# Adafruit_NeoPXL8_Wing.net
KiCad netlist of a schematic drawn in EAGLE
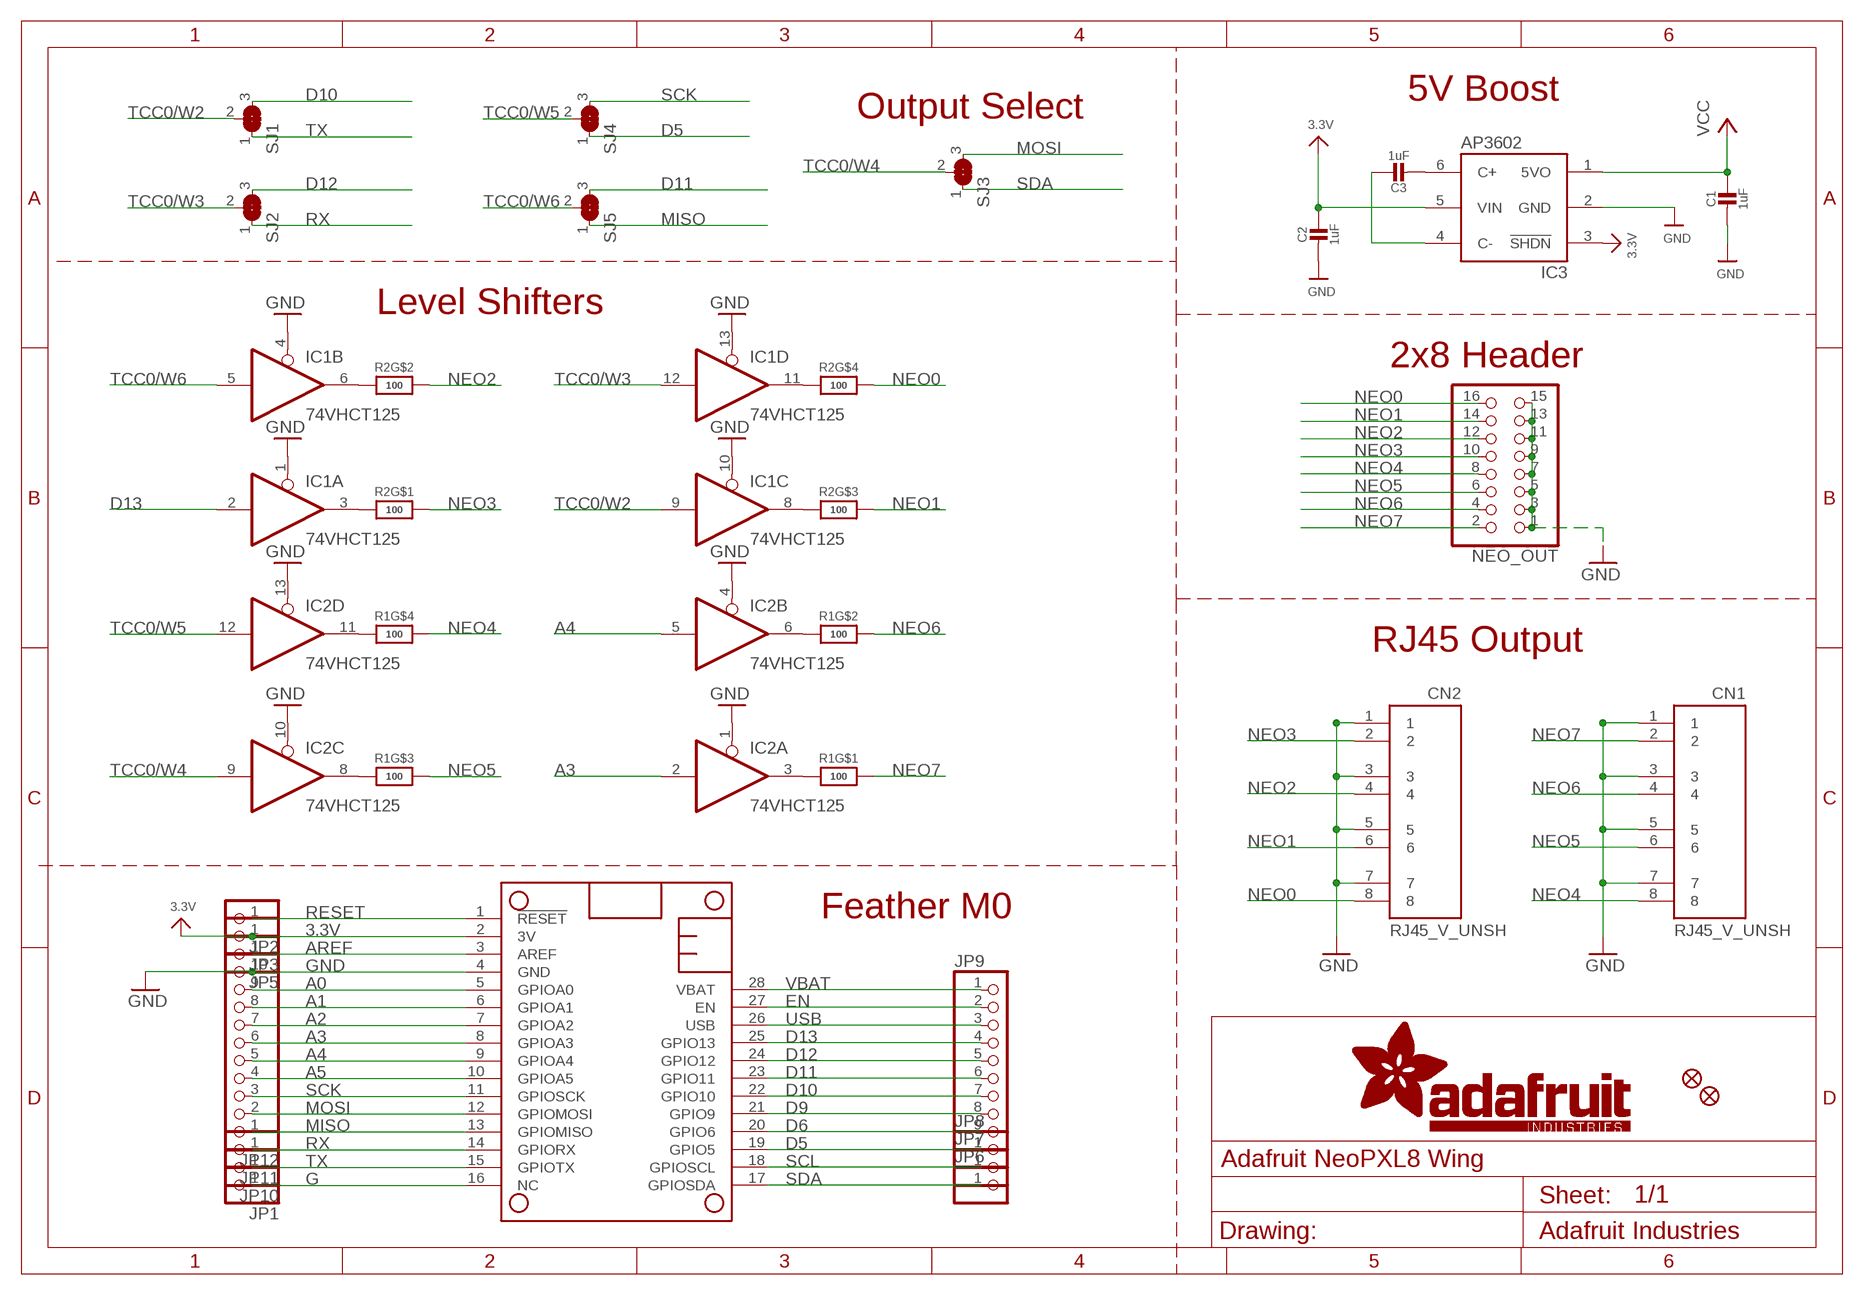
[diagram p0: schematic, sheet 1]

(export (version "E")
  (design (tool "Eeschema 10.0.6"))
  (components
    (comp (ref "C1")
      (value "1uF")
      (footprint "eagle-import:0603-NO")
      (libsource (lib "eagle-import") (part "CAP_CERAMIC0603_NO"))
    )
    (comp (ref "C2")
      (value "1uF")
      (footprint "eagle-import:0603-NO")
      (libsource (lib "eagle-import") (part "CAP_CERAMIC0603_NO"))
    )
    (comp (ref "C3")
      (value "1uF")
      (footprint "eagle-import:0603-NO")
      (libsource (lib "eagle-import") (part "CAP_CERAMIC0603_NO"))
    )
    (comp (ref "CN1")
      (value "RJ45_V_UNSH")
      (footprint "eagle-import:RJ45_VERTICAL_UNSHIELDED")
      (libsource (lib "eagle-import") (part "RJ45_V_UNSH"))
    )
    (comp (ref "CN2")
      (value "RJ45_V_UNSH")
      (footprint "eagle-import:RJ45_VERTICAL_UNSHIELDED")
      (libsource (lib "eagle-import") (part "RJ45_V_UNSH"))
    )
    (comp (ref "FID1")
      (value "FIDUCIAL_1MM")
      (footprint "eagle-import:FIDUCIAL_1MM")
      (libsource (lib "eagle-import") (part "FIDUCIAL_1MM"))
    )
    (comp (ref "FID2")
      (value "FIDUCIAL_1MM")
      (footprint "eagle-import:FIDUCIAL_1MM")
      (libsource (lib "eagle-import") (part "FIDUCIAL_1MM"))
    )
    (comp (ref "IC1")
      (value "74VHCT125")
      (footprint "eagle-import:TSSOP14")
      (libsource (lib "eagle-import") (part "74125PWABT"))
    )
    (comp (ref "IC2")
      (value "74VHCT125")
      (footprint "eagle-import:TSSOP14")
      (libsource (lib "eagle-import") (part "74125PWABT"))
    )
    (comp (ref "IC3")
      (value "AP3602")
      (footprint "eagle-import:SOT23-6")
      (libsource (lib "eagle-import") (part "AP3602"))
    )
    (comp (ref "JP1")
      (value "HEADER-1X1ROUND")
      (footprint "eagle-import:1X01_ROUND")
      (libsource (lib "eagle-import") (part "HEADER-1X1ROUND"))
    )
    (comp (ref "JP2")
      (value "HEADER-1X1ROUND")
      (footprint "eagle-import:1X01_ROUND")
      (libsource (lib "eagle-import") (part "HEADER-1X1ROUND"))
    )
    (comp (ref "JP3")
      (value "HEADER-1X1ROUND")
      (footprint "eagle-import:1X01_ROUND")
      (libsource (lib "eagle-import") (part "HEADER-1X1ROUND"))
    )
    (comp (ref "JP5")
      (value "HEADER-1X1ROUND")
      (footprint "eagle-import:1X01_ROUND")
      (libsource (lib "eagle-import") (part "HEADER-1X1ROUND"))
    )
    (comp (ref "JP6")
      (value "HEADER-1X1ROUND")
      (footprint "eagle-import:1X01_ROUND")
      (libsource (lib "eagle-import") (part "HEADER-1X1ROUND"))
    )
    (comp (ref "JP7")
      (value "HEADER-1X1ROUND")
      (footprint "eagle-import:1X01_ROUND")
      (libsource (lib "eagle-import") (part "HEADER-1X1ROUND"))
    )
    (comp (ref "JP8")
      (value "HEADER-1X1ROUND")
      (footprint "eagle-import:1X01_ROUND")
      (libsource (lib "eagle-import") (part "HEADER-1X1ROUND"))
    )
    (comp (ref "JP9")
      (value "HEADER-1X970MIL")
      (footprint "eagle-import:1X09_ROUND_70")
      (libsource (lib "eagle-import") (part "HEADER-1X970MIL"))
    )
    (comp (ref "JP10")
      (value "HEADER-1X1ROUND")
      (footprint "eagle-import:1X01_ROUND")
      (libsource (lib "eagle-import") (part "HEADER-1X1ROUND"))
    )
    (comp (ref "JP11")
      (value "HEADER-1X1ROUND")
      (footprint "eagle-import:1X01_ROUND")
      (libsource (lib "eagle-import") (part "HEADER-1X1ROUND"))
    )
    (comp (ref "JP12")
      (value "HEADER-1X10ROUND")
      (footprint "eagle-import:1X10_ROUND")
      (libsource (lib "eagle-import") (part "HEADER-1X10ROUND"))
    )
    (comp (ref "MS1")
      (value "FEATHERWING")
      (footprint "eagle-import:FEATHERWING")
      (libsource (lib "eagle-import") (part "FEATHERWING"))
    )
    (comp (ref "NEO_OUT")
      (value "HEADER-2X8")
      (footprint "eagle-import:2X08")
      (libsource (lib "eagle-import") (part "HEADER-2X8"))
    )
    (comp (ref "R1")
      (value "100")
      (footprint "eagle-import:RESPACK_4X0603")
      (libsource (lib "eagle-import") (part "RESISTOR_4PACK"))
    )
    (comp (ref "R2")
      (value "100")
      (footprint "eagle-import:RESPACK_4X0603")
      (libsource (lib "eagle-import") (part "RESISTOR_4PACK"))
    )
    (comp (ref "SJ1")
      (value "SOLDERJUMPER_2WAY")
      (footprint "eagle-import:SOLDERJUMPER_2WAY_OPEN_NOPASTE")
      (libsource (lib "eagle-import") (part "SOLDERJUMPER_2WAY"))
    )
    (comp (ref "SJ2")
      (value "SOLDERJUMPER_2WAY")
      (footprint "eagle-import:SOLDERJUMPER_2WAY_OPEN_NOPASTE")
      (libsource (lib "eagle-import") (part "SOLDERJUMPER_2WAY"))
    )
    (comp (ref "SJ3")
      (value "SOLDERJUMPER_2WAY")
      (footprint "eagle-import:SOLDERJUMPER_2WAY_OPEN_NOPASTE")
      (libsource (lib "eagle-import") (part "SOLDERJUMPER_2WAY"))
    )
    (comp (ref "SJ4")
      (value "SOLDERJUMPER_2WAY")
      (footprint "eagle-import:SOLDERJUMPER_2WAY_OPEN_NOPASTE")
      (libsource (lib "eagle-import") (part "SOLDERJUMPER_2WAY"))
    )
    (comp (ref "SJ5")
      (value "SOLDERJUMPER_2WAY")
      (footprint "eagle-import:SOLDERJUMPER_2WAY_OPEN_NOPASTE")
      (libsource (lib "eagle-import") (part "SOLDERJUMPER_2WAY"))
    )
  )
  (nets
    (net (code "1") (name "/A0") (class "Default")
      (node (ref "JP12") (pin "9") (pinfunction "9_9") (pintype "passive"))
      (node (ref "MS1") (pin "5") (pinfunction "GPIOA0_5") (pintype "bidirectional"))
    )
    (net (code "2") (name "/A1") (class "Default")
      (node (ref "JP12") (pin "8") (pinfunction "8_8") (pintype "passive"))
      (node (ref "MS1") (pin "6") (pinfunction "GPIOA1_6") (pintype "bidirectional"))
    )
    (net (code "3") (name "/A2") (class "Default")
      (node (ref "JP12") (pin "7") (pinfunction "7_7") (pintype "passive"))
      (node (ref "MS1") (pin "7") (pinfunction "GPIOA2_7") (pintype "bidirectional"))
    )
    (net (code "4") (name "/A3") (class "Default")
      (node (ref "IC2") (pin "2") (pinfunction "I_2") (pintype "input"))
      (node (ref "JP12") (pin "6") (pinfunction "6_6") (pintype "passive"))
      (node (ref "MS1") (pin "8") (pinfunction "GPIOA3_8") (pintype "bidirectional"))
    )
    (net (code "5") (name "/A4") (class "Default")
      (node (ref "IC2") (pin "5") (pinfunction "I_5") (pintype "input"))
      (node (ref "JP12") (pin "5") (pinfunction "5_5") (pintype "passive"))
      (node (ref "MS1") (pin "9") (pinfunction "GPIOA4_9") (pintype "bidirectional"))
    )
    (net (code "6") (name "/A5") (class "Default")
      (node (ref "JP12") (pin "4") (pinfunction "4_4") (pintype "passive"))
      (node (ref "MS1") (pin "10") (pinfunction "GPIOA5_10") (pintype "bidirectional"))
    )
    (net (code "7") (name "/AREF") (class "Default")
      (node (ref "JP5") (pin "1") (pinfunction "1_1") (pintype "passive"))
      (node (ref "MS1") (pin "3") (pinfunction "AREF_3") (pintype "passive"))
    )
    (net (code "8") (name "/D5") (class "Default")
      (node (ref "JP8") (pin "1") (pinfunction "1_1") (pintype "passive"))
      (node (ref "MS1") (pin "19") (pinfunction "GPIO5_19") (pintype "bidirectional"))
      (node (ref "SJ4") (pin "1") (pinfunction "1_1") (pintype "passive"))
    )
    (net (code "9") (name "/D6") (class "Default")
      (node (ref "JP9") (pin "9") (pinfunction "9_9") (pintype "passive"))
      (node (ref "MS1") (pin "20") (pinfunction "GPIO6_20") (pintype "bidirectional"))
    )
    (net (code "10") (name "/D9") (class "Default")
      (node (ref "JP9") (pin "8") (pinfunction "8_8") (pintype "passive"))
      (node (ref "MS1") (pin "21") (pinfunction "GPIO9_21") (pintype "bidirectional"))
    )
    (net (code "11") (name "/D10") (class "Default")
      (node (ref "JP9") (pin "7") (pinfunction "7_7") (pintype "passive"))
      (node (ref "MS1") (pin "22") (pinfunction "GPIO10_22") (pintype "bidirectional"))
      (node (ref "SJ1") (pin "3") (pinfunction "3_3") (pintype "passive"))
    )
    (net (code "12") (name "/D11") (class "Default")
      (node (ref "JP9") (pin "6") (pinfunction "6_6") (pintype "passive"))
      (node (ref "MS1") (pin "23") (pinfunction "GPIO11_23") (pintype "bidirectional"))
      (node (ref "SJ5") (pin "3") (pinfunction "3_3") (pintype "passive"))
    )
    (net (code "13") (name "/D12") (class "Default")
      (node (ref "JP9") (pin "5") (pinfunction "5_5") (pintype "passive"))
      (node (ref "MS1") (pin "24") (pinfunction "GPIO12_24") (pintype "bidirectional"))
      (node (ref "SJ2") (pin "3") (pinfunction "3_3") (pintype "passive"))
    )
    (net (code "14") (name "/D13") (class "Default")
      (node (ref "IC1") (pin "2") (pinfunction "I_2") (pintype "input"))
      (node (ref "JP9") (pin "4") (pinfunction "4_4") (pintype "passive"))
      (node (ref "MS1") (pin "25") (pinfunction "GPIO13_25") (pintype "bidirectional"))
    )
    (net (code "15") (name "/EN") (class "Default")
      (node (ref "JP9") (pin "2") (pinfunction "2_2") (pintype "passive"))
      (node (ref "MS1") (pin "27") (pinfunction "EN_27") (pintype "passive"))
    )
    (net (code "16") (name "/G") (class "Default")
      (node (ref "JP1") (pin "1") (pinfunction "1_1") (pintype "passive"))
      (node (ref "MS1") (pin "16") (pinfunction "NC_16") (pintype "passive"))
    )
    (net (code "17") (name "/MISO") (class "Default")
      (node (ref "JP12") (pin "1") (pinfunction "1_1") (pintype "passive"))
      (node (ref "MS1") (pin "13") (pinfunction "GPIOMISO_13") (pintype "bidirectional"))
      (node (ref "SJ5") (pin "1") (pinfunction "1_1") (pintype "passive"))
    )
    (net (code "18") (name "/MOSI") (class "Default")
      (node (ref "JP12") (pin "2") (pinfunction "2_2") (pintype "passive"))
      (node (ref "MS1") (pin "12") (pinfunction "GPIOMOSI_12") (pintype "bidirectional"))
      (node (ref "SJ3") (pin "3") (pinfunction "3_3") (pintype "passive"))
    )
    (net (code "19") (name "/NEO0") (class "Default")
      (node (ref "CN2") (pin "8") (pinfunction "8_8") (pintype "bidirectional"))
      (node (ref "NEO_OUT") (pin "16") (pinfunction "16_16") (pintype "passive"))
      (node (ref "R2") (pin "5") (pinfunction "2_5") (pintype "passive"))
    )
    (net (code "20") (name "/NEO1") (class "Default")
      (node (ref "CN2") (pin "6") (pinfunction "6_6") (pintype "bidirectional"))
      (node (ref "NEO_OUT") (pin "14") (pinfunction "14_14") (pintype "passive"))
      (node (ref "R2") (pin "6") (pinfunction "2_6") (pintype "passive"))
    )
    (net (code "21") (name "/NEO2") (class "Default")
      (node (ref "CN2") (pin "4") (pinfunction "4_4") (pintype "bidirectional"))
      (node (ref "NEO_OUT") (pin "12") (pinfunction "12_12") (pintype "passive"))
      (node (ref "R2") (pin "7") (pinfunction "2_7") (pintype "passive"))
    )
    (net (code "22") (name "/NEO3") (class "Default")
      (node (ref "CN2") (pin "2") (pinfunction "2_2") (pintype "bidirectional"))
      (node (ref "NEO_OUT") (pin "10") (pinfunction "10_10") (pintype "passive"))
      (node (ref "R2") (pin "8") (pinfunction "2_8") (pintype "passive"))
    )
    (net (code "23") (name "/NEO4") (class "Default")
      (node (ref "CN1") (pin "8") (pinfunction "8_8") (pintype "bidirectional"))
      (node (ref "NEO_OUT") (pin "8") (pinfunction "8_8") (pintype "passive"))
      (node (ref "R1") (pin "5") (pinfunction "2_5") (pintype "passive"))
    )
    (net (code "24") (name "/NEO5") (class "Default")
      (node (ref "CN1") (pin "6") (pinfunction "6_6") (pintype "bidirectional"))
      (node (ref "NEO_OUT") (pin "6") (pinfunction "6_6") (pintype "passive"))
      (node (ref "R1") (pin "6") (pinfunction "2_6") (pintype "passive"))
    )
    (net (code "25") (name "/NEO6") (class "Default")
      (node (ref "CN1") (pin "4") (pinfunction "4_4") (pintype "bidirectional"))
      (node (ref "NEO_OUT") (pin "4") (pinfunction "4_4") (pintype "passive"))
      (node (ref "R1") (pin "7") (pinfunction "2_7") (pintype "passive"))
    )
    (net (code "26") (name "/NEO7") (class "Default")
      (node (ref "CN1") (pin "2") (pinfunction "2_2") (pintype "bidirectional"))
      (node (ref "NEO_OUT") (pin "2") (pinfunction "2_2") (pintype "passive"))
      (node (ref "R1") (pin "8") (pinfunction "2_8") (pintype "passive"))
    )
    (net (code "27") (name "/RESET") (class "Default")
      (node (ref "JP2") (pin "1") (pinfunction "1_1") (pintype "passive"))
      (node (ref "MS1") (pin "1") (pinfunction "~{RESET}_1") (pintype "input"))
    )
    (net (code "28") (name "/RX") (class "Default")
      (node (ref "JP11") (pin "1") (pinfunction "1_1") (pintype "passive"))
      (node (ref "MS1") (pin "14") (pinfunction "GPIORX_14") (pintype "bidirectional"))
      (node (ref "SJ2") (pin "1") (pinfunction "1_1") (pintype "passive"))
    )
    (net (code "29") (name "/SCK") (class "Default")
      (node (ref "JP12") (pin "3") (pinfunction "3_3") (pintype "passive"))
      (node (ref "MS1") (pin "11") (pinfunction "GPIOSCK_11") (pintype "bidirectional"))
      (node (ref "SJ4") (pin "3") (pinfunction "3_3") (pintype "passive"))
    )
    (net (code "30") (name "/SCL") (class "Default")
      (node (ref "JP7") (pin "1") (pinfunction "1_1") (pintype "passive"))
      (node (ref "MS1") (pin "18") (pinfunction "GPIOSCL_18") (pintype "bidirectional"))
    )
    (net (code "31") (name "/SDA") (class "Default")
      (node (ref "JP6") (pin "1") (pinfunction "1_1") (pintype "passive"))
      (node (ref "MS1") (pin "17") (pinfunction "GPIOSDA_17") (pintype "bidirectional"))
      (node (ref "SJ3") (pin "1") (pinfunction "1_1") (pintype "passive"))
    )
    (net (code "32") (name "/TCC0{slash}W2") (class "Default")
      (node (ref "IC1") (pin "9") (pinfunction "I_9") (pintype "input"))
      (node (ref "SJ1") (pin "2") (pinfunction "2_2") (pintype "passive"))
    )
    (net (code "33") (name "/TCC0{slash}W3") (class "Default")
      (node (ref "IC1") (pin "12") (pinfunction "I_12") (pintype "input"))
      (node (ref "SJ2") (pin "2") (pinfunction "2_2") (pintype "passive"))
    )
    (net (code "34") (name "/TCC0{slash}W4") (class "Default")
      (node (ref "IC2") (pin "9") (pinfunction "I_9") (pintype "input"))
      (node (ref "SJ3") (pin "2") (pinfunction "2_2") (pintype "passive"))
    )
    (net (code "35") (name "/TCC0{slash}W5") (class "Default")
      (node (ref "IC2") (pin "12") (pinfunction "I_12") (pintype "input"))
      (node (ref "SJ4") (pin "2") (pinfunction "2_2") (pintype "passive"))
    )
    (net (code "36") (name "/TCC0{slash}W6") (class "Default")
      (node (ref "IC1") (pin "5") (pinfunction "I_5") (pintype "input"))
      (node (ref "SJ5") (pin "2") (pinfunction "2_2") (pintype "passive"))
    )
    (net (code "37") (name "/TX") (class "Default")
      (node (ref "JP10") (pin "1") (pinfunction "1_1") (pintype "passive"))
      (node (ref "MS1") (pin "15") (pinfunction "GPIOTX_15") (pintype "bidirectional"))
      (node (ref "SJ1") (pin "1") (pinfunction "1_1") (pintype "passive"))
    )
    (net (code "38") (name "/USB") (class "Default")
      (node (ref "JP9") (pin "3") (pinfunction "3_3") (pintype "passive"))
      (node (ref "MS1") (pin "26") (pinfunction "USB_26") (pintype "power_in"))
    )
    (net (code "39") (name "/VBAT") (class "Default")
      (node (ref "JP9") (pin "1") (pinfunction "1_1") (pintype "passive"))
      (node (ref "MS1") (pin "28") (pinfunction "VBAT_28") (pintype "power_in"))
    )
    (net (code "40") (name "3.3V") (class "Default")
      (node (ref "C2") (pin "1") (pinfunction "1_1") (pintype "passive"))
      (node (ref "IC3") (pin "3") (pinfunction "~{SHDN}_3") (pintype "input"))
      (node (ref "IC3") (pin "5") (pinfunction "VIN_5") (pintype "power_in"))
      (node (ref "JP3") (pin "1") (pinfunction "1_1") (pintype "passive"))
      (node (ref "MS1") (pin "2") (pinfunction "3V_2") (pintype "power_in"))
    )
    (net (code "41") (name "GND") (class "Default")
      (node (ref "C1") (pin "2") (pinfunction "2_2") (pintype "passive"))
      (node (ref "C2") (pin "2") (pinfunction "2_2") (pintype "passive"))
      (node (ref "CN1") (pin "1") (pinfunction "1_1") (pintype "bidirectional"))
      (node (ref "CN1") (pin "3") (pinfunction "3_3") (pintype "bidirectional"))
      (node (ref "CN1") (pin "5") (pinfunction "5_5") (pintype "bidirectional"))
      (node (ref "CN1") (pin "7") (pinfunction "7_7") (pintype "bidirectional"))
      (node (ref "CN2") (pin "1") (pinfunction "1_1") (pintype "bidirectional"))
      (node (ref "CN2") (pin "3") (pinfunction "3_3") (pintype "bidirectional"))
      (node (ref "CN2") (pin "5") (pinfunction "5_5") (pintype "bidirectional"))
      (node (ref "CN2") (pin "7") (pinfunction "7_7") (pintype "bidirectional"))
      (node (ref "IC1") (pin "1") (pinfunction "OE_1") (pintype "input"))
      (node (ref "IC1") (pin "10") (pinfunction "OE_10") (pintype "input"))
      (node (ref "IC1") (pin "13") (pinfunction "OE_13") (pintype "input"))
      (node (ref "IC1") (pin "4") (pinfunction "OE_4") (pintype "input"))
      (node (ref "IC2") (pin "1") (pinfunction "OE_1") (pintype "input"))
      (node (ref "IC2") (pin "10") (pinfunction "OE_10") (pintype "input"))
      (node (ref "IC2") (pin "13") (pinfunction "OE_13") (pintype "input"))
      (node (ref "IC2") (pin "4") (pinfunction "OE_4") (pintype "input"))
      (node (ref "IC3") (pin "2") (pinfunction "GND_2") (pintype "power_in"))
      (node (ref "JP12") (pin "10") (pinfunction "10_10") (pintype "passive"))
      (node (ref "MS1") (pin "4") (pinfunction "GND_4") (pintype "power_in"))
      (node (ref "NEO_OUT") (pin "1") (pinfunction "1_1") (pintype "passive"))
      (node (ref "NEO_OUT") (pin "11") (pinfunction "11_11") (pintype "passive"))
      (node (ref "NEO_OUT") (pin "13") (pinfunction "13_13") (pintype "passive"))
      (node (ref "NEO_OUT") (pin "15") (pinfunction "15_15") (pintype "passive"))
      (node (ref "NEO_OUT") (pin "3") (pinfunction "3_3") (pintype "passive"))
      (node (ref "NEO_OUT") (pin "5") (pinfunction "5_5") (pintype "passive"))
      (node (ref "NEO_OUT") (pin "7") (pinfunction "7_7") (pintype "passive"))
      (node (ref "NEO_OUT") (pin "9") (pinfunction "9_9") (pintype "passive"))
    )
    (net (code "42") (name "Net-(IC1A-O)") (class "Default")
      (node (ref "IC1") (pin "3") (pinfunction "O_3") (pintype "tri_state"))
      (node (ref "R2") (pin "1") (pinfunction "1_1") (pintype "passive"))
    )
    (net (code "43") (name "Net-(IC1B-O)") (class "Default")
      (node (ref "IC1") (pin "6") (pinfunction "O_6") (pintype "tri_state"))
      (node (ref "R2") (pin "2") (pinfunction "1_2") (pintype "passive"))
    )
    (net (code "44") (name "Net-(IC1C-O)") (class "Default")
      (node (ref "IC1") (pin "8") (pinfunction "O_8") (pintype "tri_state"))
      (node (ref "R2") (pin "3") (pinfunction "1_3") (pintype "passive"))
    )
    (net (code "45") (name "Net-(IC1D-O)") (class "Default")
      (node (ref "IC1") (pin "11") (pinfunction "O_11") (pintype "tri_state"))
      (node (ref "R2") (pin "4") (pinfunction "1_4") (pintype "passive"))
    )
    (net (code "46") (name "Net-(IC2A-O)") (class "Default")
      (node (ref "IC2") (pin "3") (pinfunction "O_3") (pintype "tri_state"))
      (node (ref "R1") (pin "1") (pinfunction "1_1") (pintype "passive"))
    )
    (net (code "47") (name "Net-(IC2B-O)") (class "Default")
      (node (ref "IC2") (pin "6") (pinfunction "O_6") (pintype "tri_state"))
      (node (ref "R1") (pin "2") (pinfunction "1_2") (pintype "passive"))
    )
    (net (code "48") (name "Net-(IC2C-O)") (class "Default")
      (node (ref "IC2") (pin "8") (pinfunction "O_8") (pintype "tri_state"))
      (node (ref "R1") (pin "3") (pinfunction "1_3") (pintype "passive"))
    )
    (net (code "49") (name "Net-(IC2D-O)") (class "Default")
      (node (ref "IC2") (pin "11") (pinfunction "O_11") (pintype "tri_state"))
      (node (ref "R1") (pin "4") (pinfunction "1_4") (pintype "passive"))
    )
    (net (code "50") (name "Net-(IC3-C+)") (class "Default")
      (node (ref "C3") (pin "2") (pinfunction "2_2") (pintype "passive"))
      (node (ref "IC3") (pin "6") (pinfunction "C+_6") (pintype "bidirectional"))
    )
    (net (code "51") (name "Net-(IC3-C-)") (class "Default")
      (node (ref "C3") (pin "1") (pinfunction "1_1") (pintype "passive"))
      (node (ref "IC3") (pin "4") (pinfunction "C-_4") (pintype "bidirectional"))
    )
    (net (code "52") (name "VCC") (class "Default")
      (node (ref "C1") (pin "1") (pinfunction "1_1") (pintype "passive"))
      (node (ref "IC3") (pin "1") (pinfunction "5VO_1") (pintype "power_in"))
    )
  )
)
